# EC3mini.net
KiCad netlist of a schematic drawn in Altium Designer
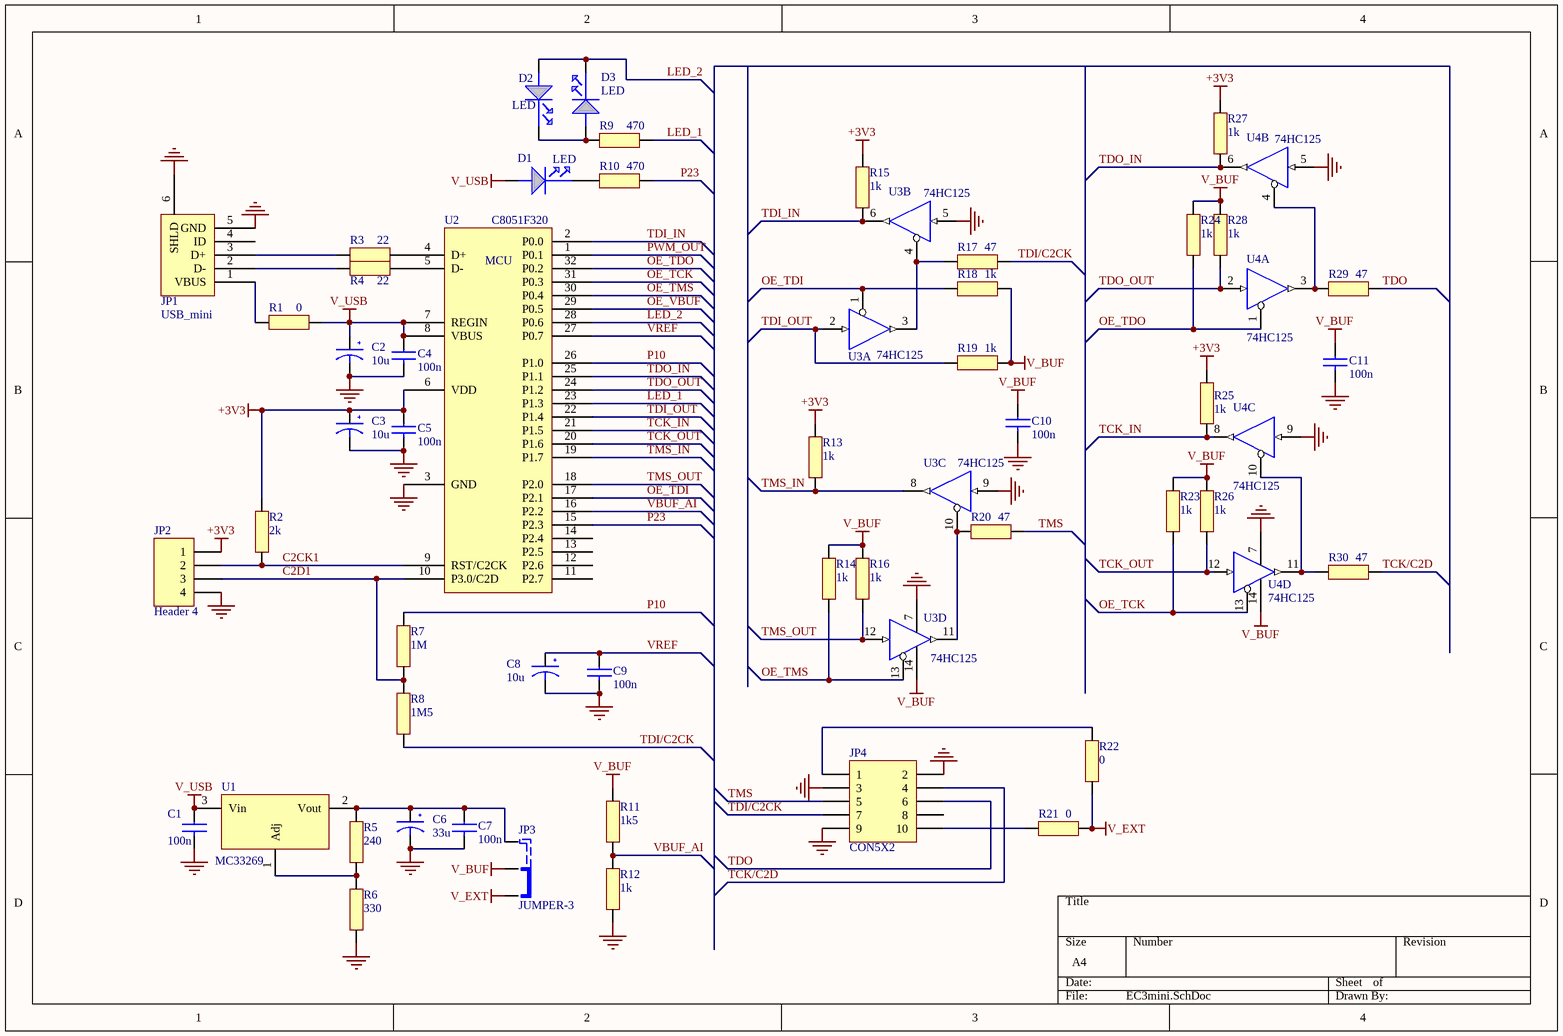
[diagram p0: EC3mini.SchDoc]

(export (version "E")
  (design (tool "Eeschema 10.0.6"))
  (components
    (comp (ref "C1") (value "100n") (footprint "C-0805") (libsource (lib "RCS-Discret") (part "C")))
    (comp (ref "C2") (value "10u") (footprint "TANTAL-A") (libsource (lib "RCS-Discret") (part "C-EL-TAN")))
    (comp (ref "C3") (value "10u") (footprint "TANTAL-A") (libsource (lib "RCS-Discret") (part "C-EL-TAN")))
    (comp (ref "C4") (value "100n") (footprint "C-0805") (libsource (lib "RCS-Discret") (part "C")))
    (comp (ref "C5") (value "100n") (footprint "C-0805") (libsource (lib "RCS-Discret") (part "C")))
    (comp (ref "C6")
      (value "33u")
      (footprint "TANTAL-B(3528)")
      (libsource (lib "RCS-Discret") (part "C-EL-TAN"))
    )
    (comp (ref "C7") (value "100n") (footprint "C-0805") (libsource (lib "RCS-Discret") (part "C")))
    (comp (ref "C8") (value "10u") (footprint "TANTAL-A") (libsource (lib "RCS-Discret") (part "C-EL-TAN")))
    (comp (ref "C9") (value "100n") (footprint "C-0805") (libsource (lib "RCS-Discret") (part "C")))
    (comp (ref "C10") (value "100n") (footprint "C-0805") (libsource (lib "RCS-Discret") (part "C")))
    (comp (ref "C11") (value "100n") (footprint "C-0805") (libsource (lib "RCS-Discret") (part "C")))
    (comp (ref "D1") (value "LED") (footprint "LED-DIP-1") (libsource (lib "RCS-Discret") (part "LED")))
    (comp (ref "D2") (value "LED") (footprint "LED-DIP-1") (libsource (lib "RCS-Discret") (part "LED")))
    (comp (ref "D3") (value "LED") (footprint "LED-DIP-1") (libsource (lib "RCS-Discret") (part "LED")))
    (comp (ref "JP1")
      (value "USB_mini")
      (footprint "miniUSBsmd")
      (libsource (lib "ISPMKII") (part "USB_mini"))
    )
    (comp (ref "JP2")
      (value "Header 4")
      (footprint "HDR1X4")
      (description "Header, 4-Pin")
      (fields (field (name "PUBLISHER") "Altium Limited"))
      (libsource (lib "Miscellaneous Connectors") (part "Header 4"))
    )
    (comp (ref "JP3")
      (value "JUMPER-3")
      (footprint "IDC1-3P")
      (description "Jumper")
      (libsource (lib "RCS-Connect&pushe") (part "JUMPER-3"))
    )
    (comp (ref "JP4")
      (value "CON5X2")
      (footprint "IDC2-5P")
      (libsource (lib "RCS-Connect&pushe") (part "CON5X2"))
    )
    (comp (ref "R1") (value "0") (footprint "R-1206") (libsource (lib "") (part "R_1")))
    (comp (ref "R2") (value "2k") (footprint "R-0805") (libsource (lib "RCS-Discret") (part "R")))
    (comp (ref "R3") (value "22") (footprint "R-0805") (libsource (lib "") (part "R_1")))
    (comp (ref "R4") (value "22") (footprint "R-0805") (libsource (lib "") (part "R_1")))
    (comp (ref "R5") (value "240") (footprint "R-0805") (libsource (lib "RCS-Discret") (part "R")))
    (comp (ref "R6") (value "330") (footprint "R-0805") (libsource (lib "RCS-Discret") (part "R")))
    (comp (ref "R7") (value "1M") (footprint "R-0805") (libsource (lib "RCS-Discret") (part "R")))
    (comp (ref "R8") (value "1M5") (footprint "R-0805") (libsource (lib "RCS-Discret") (part "R")))
    (comp (ref "R9") (value "470") (footprint "R-0805") (libsource (lib "") (part "R_1")))
    (comp (ref "R10") (value "470") (footprint "R-0805") (libsource (lib "") (part "R_1")))
    (comp (ref "R11") (value "1k5") (footprint "R-0805") (libsource (lib "RCS-Discret") (part "R")))
    (comp (ref "R12") (value "1k") (footprint "R-0805") (libsource (lib "RCS-Discret") (part "R")))
    (comp (ref "R13") (value "1k") (footprint "R-0805") (libsource (lib "RCS-Discret") (part "R")))
    (comp (ref "R14") (value "1k") (footprint "R-0805") (libsource (lib "RCS-Discret") (part "R")))
    (comp (ref "R15") (value "1k") (footprint "R-0805") (libsource (lib "RCS-Discret") (part "R")))
    (comp (ref "R16") (value "1k") (footprint "R-0805") (libsource (lib "RCS-Discret") (part "R")))
    (comp (ref "R17") (value "47") (footprint "R-0805") (libsource (lib "") (part "R_1")))
    (comp (ref "R18") (value "1k") (footprint "R-0805") (libsource (lib "") (part "R_1")))
    (comp (ref "R19") (value "1k") (footprint "R-0805") (libsource (lib "") (part "R_1")))
    (comp (ref "R20") (value "47") (footprint "R-0805") (libsource (lib "") (part "R_1")))
    (comp (ref "R21") (value "0") (footprint "R-0805") (libsource (lib "") (part "R_1")))
    (comp (ref "R22") (value "0") (footprint "R-0805") (libsource (lib "RCS-Discret") (part "R")))
    (comp (ref "R23") (value "1k") (footprint "R-0805") (libsource (lib "RCS-Discret") (part "R")))
    (comp (ref "R24") (value "1k") (footprint "R-0805") (libsource (lib "RCS-Discret") (part "R")))
    (comp (ref "R25") (value "1k") (footprint "R-0805") (libsource (lib "RCS-Discret") (part "R")))
    (comp (ref "R26") (value "1k") (footprint "R-0805") (libsource (lib "RCS-Discret") (part "R")))
    (comp (ref "R27") (value "1k") (footprint "R-0805") (libsource (lib "RCS-Discret") (part "R")))
    (comp (ref "R28") (value "1k") (footprint "R-0805") (libsource (lib "RCS-Discret") (part "R")))
    (comp (ref "R29") (value "47") (footprint "R-0805") (libsource (lib "") (part "R_1")))
    (comp (ref "R30") (value "47") (footprint "R-0805") (libsource (lib "") (part "R_1")))
    (comp (ref "U1")
      (value "MC33269")
      (footprint "SOT-428-(D-PAK)")
      (description "low dropout adjustable positive voltage regulators")
      (libsource (lib "RCS-IMS") (part "MC33269"))
    )
    (comp (ref "U2") (value "C8051F320") (footprint "QFP32") (libsource (lib "RCS-IMS") (part "C8051F320")))
    (comp (ref "U3")
      (value "74HC125")
      (footprint "SO14-(SOT-108-1)")
      (description "Four Buffers with Enable for HiZ state output")
      (libsource (lib "RCS-IMS") (part "74HC125"))
    )
    (comp (ref "U4")
      (value "74HC125")
      (footprint "SO14-(SOT-108-1)")
      (description "Four Buffers with Enable for HiZ state output")
      (libsource (lib "RCS-IMS") (part "74HC125"))
    )
  )
  (nets
    (net (code "1") (name "+3V3") (class "Default")
      (node (ref "C3") (pin "2") (pinfunction "+_2") (pintype "passive"))
      (node (ref "C5") (pin "1") (pinfunction "1_1") (pintype "passive"))
      (node (ref "JP2") (pin "1") (pinfunction "1_1") (pintype "passive"))
      (node (ref "R13") (pin "1") (pinfunction "1_1") (pintype "passive"))
      (node (ref "R15") (pin "1") (pinfunction "1_1") (pintype "passive"))
      (node (ref "R2") (pin "1") (pinfunction "1_1") (pintype "passive"))
      (node (ref "R25") (pin "1") (pinfunction "1_1") (pintype "passive"))
      (node (ref "R27") (pin "1") (pinfunction "1_1") (pintype "passive"))
      (node (ref "U2") (pin "6") (pinfunction "VDD_6") (pintype "passive"))
    )
    (net (code "2") (name "/C2CK1") (class "Default")
      (node (ref "JP2") (pin "2") (pinfunction "2_2") (pintype "passive"))
      (node (ref "R2") (pin "2") (pinfunction "2_2") (pintype "passive"))
      (node (ref "U2") (pin "9") (pinfunction "RST/C2CK_9") (pintype "passive"))
    )
    (net (code "3") (name "/C2D1") (class "Default")
      (node (ref "JP2") (pin "3") (pinfunction "3_3") (pintype "passive"))
      (node (ref "R7") (pin "2") (pinfunction "2_2") (pintype "passive"))
      (node (ref "R8") (pin "1") (pinfunction "1_1") (pintype "passive"))
      (node (ref "U2") (pin "10") (pinfunction "P3.0/C2D_10") (pintype "passive"))
    )
    (net (code "4") (name "/LED_1") (class "Default")
      (node (ref "R9") (pin "2") (pinfunction "2_2") (pintype "passive"))
      (node (ref "U2") (pin "23") (pinfunction "P1.3_23") (pintype "passive"))
    )
    (net (code "5") (name "/LED_2") (class "Default")
      (node (ref "D2") (pin "A") (pinfunction "ANODE_A") (pintype "passive"))
      (node (ref "D3") (pin "K") (pinfunction "CATHODE_K") (pintype "passive"))
      (node (ref "U2") (pin "28") (pinfunction "P0.6_28") (pintype "passive"))
    )
    (net (code "6") (name "/OE_TCK") (class "Default")
      (node (ref "R23") (pin "2") (pinfunction "2_2") (pintype "passive"))
      (node (ref "U2") (pin "31") (pinfunction "P0.3_31") (pintype "passive"))
      (node (ref "U4") (pin "13") (pinfunction "~{-Ed}_13") (pintype "passive"))
    )
    (net (code "7") (name "/OE_TDI") (class "Default")
      (node (ref "R18") (pin "1") (pinfunction "1_1") (pintype "passive"))
      (node (ref "U2") (pin "17") (pinfunction "P2.1_17") (pintype "passive"))
      (node (ref "U3") (pin "1") (pinfunction "~{-Ea}_1") (pintype "passive"))
    )
    (net (code "8") (name "/OE_TDO") (class "Default")
      (node (ref "R24") (pin "2") (pinfunction "2_2") (pintype "passive"))
      (node (ref "U2") (pin "32") (pinfunction "P0.2_32") (pintype "passive"))
      (node (ref "U4") (pin "1") (pinfunction "~{-Ea}_1") (pintype "passive"))
    )
    (net (code "9") (name "/OE_TMS") (class "Default")
      (node (ref "R14") (pin "2") (pinfunction "2_2") (pintype "passive"))
      (node (ref "U2") (pin "30") (pinfunction "P0.4_30") (pintype "passive"))
      (node (ref "U3") (pin "13") (pinfunction "~{-Ed}_13") (pintype "passive"))
    )
    (net (code "10") (name "/OE_VBUF") (class "Default")
      (node (ref "U2") (pin "29") (pinfunction "P0.5_29") (pintype "passive"))
    )
    (net (code "11") (name "/P10") (class "Default")
      (node (ref "R7") (pin "1") (pinfunction "1_1") (pintype "passive"))
      (node (ref "U2") (pin "26") (pinfunction "P1.0_26") (pintype "passive"))
    )
    (net (code "12") (name "/P23") (class "Default")
      (node (ref "R10") (pin "2") (pinfunction "2_2") (pintype "passive"))
      (node (ref "U2") (pin "15") (pinfunction "P2.3_15") (pintype "passive"))
    )
    (net (code "13") (name "/PWM_OUT") (class "Default")
      (node (ref "U2") (pin "1") (pinfunction "P0.1_1") (pintype "passive"))
    )
    (net (code "14") (name "/TCK_IN") (class "Default")
      (node (ref "R25") (pin "2") (pinfunction "2_2") (pintype "passive"))
      (node (ref "U2") (pin "21") (pinfunction "P1.5_21") (pintype "passive"))
      (node (ref "U4") (pin "8") (pinfunction "Yc_8") (pintype "output"))
    )
    (net (code "15") (name "/TCK_OUT") (class "Default")
      (node (ref "R26") (pin "2") (pinfunction "2_2") (pintype "passive"))
      (node (ref "U2") (pin "20") (pinfunction "P1.6_20") (pintype "passive"))
      (node (ref "U4") (pin "12") (pinfunction "D_12") (pintype "input"))
    )
    (net (code "16") (name "/TCK{slash}C2D") (class "Default")
      (node (ref "JP4") (pin "4") (pinfunction "4_4") (pintype "passive"))
      (node (ref "R30") (pin "2") (pinfunction "2_2") (pintype "passive"))
    )
    (net (code "17") (name "/TDI_IN") (class "Default")
      (node (ref "R15") (pin "2") (pinfunction "2_2") (pintype "passive"))
      (node (ref "U2") (pin "2") (pinfunction "P0.0_2") (pintype "passive"))
      (node (ref "U3") (pin "6") (pinfunction "Yb_6") (pintype "output"))
    )
    (net (code "18") (name "/TDI_OUT") (class "Default")
      (node (ref "R19") (pin "1") (pinfunction "1_1") (pintype "passive"))
      (node (ref "U2") (pin "22") (pinfunction "P1.4_22") (pintype "passive"))
      (node (ref "U3") (pin "2") (pinfunction "A_2") (pintype "input"))
    )
    (net (code "19") (name "/TDI{slash}C2CK") (class "Default")
      (node (ref "JP4") (pin "7") (pinfunction "7_7") (pintype "passive"))
      (node (ref "R17") (pin "2") (pinfunction "2_2") (pintype "passive"))
      (node (ref "R8") (pin "2") (pinfunction "2_2") (pintype "passive"))
    )
    (net (code "20") (name "/TDO") (class "Default")
      (node (ref "JP4") (pin "6") (pinfunction "6_6") (pintype "passive"))
      (node (ref "R29") (pin "2") (pinfunction "2_2") (pintype "passive"))
    )
    (net (code "21") (name "/TDO_IN") (class "Default")
      (node (ref "R27") (pin "2") (pinfunction "2_2") (pintype "passive"))
      (node (ref "U2") (pin "25") (pinfunction "P1.1_25") (pintype "passive"))
      (node (ref "U4") (pin "6") (pinfunction "Yb_6") (pintype "output"))
    )
    (net (code "22") (name "/TDO_OUT") (class "Default")
      (node (ref "R28") (pin "2") (pinfunction "2_2") (pintype "passive"))
      (node (ref "U2") (pin "24") (pinfunction "P1.2_24") (pintype "passive"))
      (node (ref "U4") (pin "2") (pinfunction "A_2") (pintype "input"))
    )
    (net (code "23") (name "/TMS") (class "Default")
      (node (ref "JP4") (pin "5") (pinfunction "5_5") (pintype "passive"))
      (node (ref "R20") (pin "2") (pinfunction "2_2") (pintype "passive"))
    )
    (net (code "24") (name "/TMS_IN") (class "Default")
      (node (ref "R13") (pin "2") (pinfunction "2_2") (pintype "passive"))
      (node (ref "U2") (pin "19") (pinfunction "P1.7_19") (pintype "passive"))
      (node (ref "U3") (pin "8") (pinfunction "Yc_8") (pintype "output"))
    )
    (net (code "25") (name "/TMS_OUT") (class "Default")
      (node (ref "R16") (pin "2") (pinfunction "2_2") (pintype "passive"))
      (node (ref "U2") (pin "18") (pinfunction "P2.0_18") (pintype "passive"))
      (node (ref "U3") (pin "12") (pinfunction "D_12") (pintype "input"))
    )
    (net (code "26") (name "/VBUF_AI") (class "Default")
      (node (ref "R11") (pin "2") (pinfunction "2_2") (pintype "passive"))
      (node (ref "R12") (pin "1") (pinfunction "1_1") (pintype "passive"))
      (node (ref "U2") (pin "16") (pinfunction "P2.2_16") (pintype "passive"))
    )
    (net (code "27") (name "/VREF") (class "Default")
      (node (ref "C8") (pin "2") (pinfunction "+_2") (pintype "passive"))
      (node (ref "C9") (pin "1") (pinfunction "1_1") (pintype "passive"))
      (node (ref "U2") (pin "27") (pinfunction "P0.7_27") (pintype "passive"))
    )
    (net (code "28") (name "GND") (class "Default")
      (node (ref "C1") (pin "2") (pinfunction "2_2") (pintype "passive"))
      (node (ref "C10") (pin "2") (pinfunction "2_2") (pintype "passive"))
      (node (ref "C11") (pin "2") (pinfunction "2_2") (pintype "passive"))
      (node (ref "C2") (pin "1") (pinfunction "-_1") (pintype "passive"))
      (node (ref "C3") (pin "1") (pinfunction "-_1") (pintype "passive"))
      (node (ref "C4") (pin "2") (pinfunction "2_2") (pintype "passive"))
      (node (ref "C5") (pin "2") (pinfunction "2_2") (pintype "passive"))
      (node (ref "C6") (pin "1") (pinfunction "-_1") (pintype "passive"))
      (node (ref "C7") (pin "2") (pinfunction "2_2") (pintype "passive"))
      (node (ref "C8") (pin "1") (pinfunction "-_1") (pintype "passive"))
      (node (ref "C9") (pin "2") (pinfunction "2_2") (pintype "passive"))
      (node (ref "JP1") (pin "5") (pinfunction "GND_5") (pintype "passive"))
      (node (ref "JP1") (pin "6") (pinfunction "SHLD_6") (pintype "passive"))
      (node (ref "JP2") (pin "4") (pinfunction "4_4") (pintype "passive"))
      (node (ref "JP4") (pin "2") (pinfunction "2_2") (pintype "passive"))
      (node (ref "JP4") (pin "3") (pinfunction "3_3") (pintype "passive"))
      (node (ref "JP4") (pin "9") (pinfunction "9_9") (pintype "passive"))
      (node (ref "R12") (pin "2") (pinfunction "2_2") (pintype "passive"))
      (node (ref "R6") (pin "2") (pinfunction "2_2") (pintype "passive"))
      (node (ref "U2") (pin "3") (pinfunction "GND_3") (pintype "passive"))
      (node (ref "U3") (pin "5") (pinfunction "B_5") (pintype "input"))
      (node (ref "U3") (pin "7") (pinfunction "GND-D_7") (pintype "power_in"))
      (node (ref "U3") (pin "9") (pinfunction "C_9") (pintype "input"))
      (node (ref "U4") (pin "5") (pinfunction "B_5") (pintype "input"))
      (node (ref "U4") (pin "7") (pinfunction "GND-D_7") (pintype "power_in"))
      (node (ref "U4") (pin "9") (pinfunction "C_9") (pintype "input"))
    )
    (net (code "29") (name "Net-(C6-+)") (class "Default")
      (node (ref "C6") (pin "2") (pinfunction "+_2") (pintype "passive"))
      (node (ref "C7") (pin "1") (pinfunction "1_1") (pintype "passive"))
      (node (ref "JP3") (pin "3") (pinfunction "3_3") (pintype "passive"))
      (node (ref "R5") (pin "1") (pinfunction "1_1") (pintype "passive"))
      (node (ref "U1") (pin "2") (pinfunction "Vout_2") (pintype "passive"))
    )
    (net (code "30") (name "Net-(D1-CATHODE)") (class "Default")
      (node (ref "D1") (pin "K") (pinfunction "CATHODE_K") (pintype "passive"))
      (node (ref "R10") (pin "1") (pinfunction "1_1") (pintype "passive"))
    )
    (net (code "31") (name "Net-(D2-CATHODE)") (class "Default")
      (node (ref "D2") (pin "K") (pinfunction "CATHODE_K") (pintype "passive"))
      (node (ref "D3") (pin "A") (pinfunction "ANODE_A") (pintype "passive"))
      (node (ref "R9") (pin "1") (pinfunction "1_1") (pintype "passive"))
    )
    (net (code "32") (name "Net-(JP1-D+)") (class "Default")
      (node (ref "JP1") (pin "3") (pinfunction "D+_3") (pintype "passive"))
      (node (ref "R3") (pin "1") (pinfunction "1_1") (pintype "passive"))
    )
    (net (code "33") (name "Net-(JP1-D-)") (class "Default")
      (node (ref "JP1") (pin "2") (pinfunction "D-_2") (pintype "passive"))
      (node (ref "R4") (pin "1") (pinfunction "1_1") (pintype "passive"))
    )
    (net (code "34") (name "Net-(JP1-VBUS)") (class "Default")
      (node (ref "JP1") (pin "1") (pinfunction "VBUS_1") (pintype "passive"))
      (node (ref "R1") (pin "1") (pinfunction "1_1") (pintype "passive"))
    )
    (net (code "35") (name "Net-(JP4-Pad1)") (class "Default")
      (node (ref "JP4") (pin "1") (pinfunction "1_1") (pintype "passive"))
      (node (ref "R22") (pin "1") (pinfunction "1_1") (pintype "passive"))
    )
    (net (code "36") (name "Net-(JP4-Pad10)") (class "Default")
      (node (ref "JP4") (pin "10") (pinfunction "10_10") (pintype "passive"))
      (node (ref "R21") (pin "1") (pinfunction "1_1") (pintype "passive"))
    )
    (net (code "37") (name "Net-(U1-Adj)") (class "Default")
      (node (ref "R5") (pin "2") (pinfunction "2_2") (pintype "passive"))
      (node (ref "R6") (pin "1") (pinfunction "1_1") (pintype "passive"))
      (node (ref "U1") (pin "1") (pinfunction "Adj_1") (pintype "passive"))
    )
    (net (code "38") (name "Net-(U2-D+)") (class "Default")
      (node (ref "R3") (pin "2") (pinfunction "2_2") (pintype "passive"))
      (node (ref "U2") (pin "4") (pinfunction "D+_4") (pintype "passive"))
    )
    (net (code "39") (name "Net-(U2-D-)") (class "Default")
      (node (ref "R4") (pin "2") (pinfunction "2_2") (pintype "passive"))
      (node (ref "U2") (pin "5") (pinfunction "D-_5") (pintype "passive"))
    )
    (net (code "40") (name "Net-(U3A-Ya)") (class "Default")
      (node (ref "R17") (pin "1") (pinfunction "1_1") (pintype "passive"))
      (node (ref "U3") (pin "3") (pinfunction "Ya_3") (pintype "output"))
      (node (ref "U3") (pin "4") (pinfunction "~{-Eb}_4") (pintype "passive"))
    )
    (net (code "41") (name "Net-(U3C-~{-Ec})") (class "Default")
      (node (ref "R20") (pin "1") (pinfunction "1_1") (pintype "passive"))
      (node (ref "U3") (pin "10") (pinfunction "~{-Ec}_10") (pintype "passive"))
      (node (ref "U3") (pin "11") (pinfunction "Yd_11") (pintype "output"))
    )
    (net (code "42") (name "Net-(U4A-Ya)") (class "Default")
      (node (ref "R29") (pin "1") (pinfunction "1_1") (pintype "passive"))
      (node (ref "U4") (pin "3") (pinfunction "Ya_3") (pintype "output"))
      (node (ref "U4") (pin "4") (pinfunction "~{-Eb}_4") (pintype "passive"))
    )
    (net (code "43") (name "Net-(U4C-~{-Ec})") (class "Default")
      (node (ref "R30") (pin "1") (pinfunction "1_1") (pintype "passive"))
      (node (ref "U4") (pin "10") (pinfunction "~{-Ec}_10") (pintype "passive"))
      (node (ref "U4") (pin "11") (pinfunction "Yd_11") (pintype "output"))
    )
    (net (code "44") (name "V_BUF") (class "Default")
      (node (ref "C10") (pin "1") (pinfunction "1_1") (pintype "passive"))
      (node (ref "C11") (pin "1") (pinfunction "1_1") (pintype "passive"))
      (node (ref "JP3") (pin "2") (pinfunction "2_2") (pintype "passive"))
      (node (ref "R11") (pin "1") (pinfunction "1_1") (pintype "passive"))
      (node (ref "R14") (pin "1") (pinfunction "1_1") (pintype "passive"))
      (node (ref "R16") (pin "1") (pinfunction "1_1") (pintype "passive"))
      (node (ref "R18") (pin "2") (pinfunction "2_2") (pintype "passive"))
      (node (ref "R19") (pin "2") (pinfunction "2_2") (pintype "passive"))
      (node (ref "R23") (pin "1") (pinfunction "1_1") (pintype "passive"))
      (node (ref "R24") (pin "1") (pinfunction "1_1") (pintype "passive"))
      (node (ref "R26") (pin "1") (pinfunction "1_1") (pintype "passive"))
      (node (ref "R28") (pin "1") (pinfunction "1_1") (pintype "passive"))
      (node (ref "U3") (pin "14") (pinfunction "VCC_14") (pintype "power_in"))
      (node (ref "U4") (pin "14") (pinfunction "VCC_14") (pintype "power_in"))
    )
    (net (code "45") (name "V_EXT") (class "Default")
      (node (ref "JP3") (pin "1") (pinfunction "1_1") (pintype "passive"))
      (node (ref "R21") (pin "2") (pinfunction "2_2") (pintype "passive"))
      (node (ref "R22") (pin "2") (pinfunction "2_2") (pintype "passive"))
    )
    (net (code "46") (name "V_USB") (class "Default")
      (node (ref "C1") (pin "1") (pinfunction "1_1") (pintype "passive"))
      (node (ref "C2") (pin "2") (pinfunction "+_2") (pintype "passive"))
      (node (ref "C4") (pin "1") (pinfunction "1_1") (pintype "passive"))
      (node (ref "D1") (pin "A") (pinfunction "ANODE_A") (pintype "passive"))
      (node (ref "R1") (pin "2") (pinfunction "2_2") (pintype "passive"))
      (node (ref "U1") (pin "3") (pinfunction "Vin_3") (pintype "passive"))
      (node (ref "U2") (pin "7") (pinfunction "REGIN_7") (pintype "passive"))
      (node (ref "U2") (pin "8") (pinfunction "VBUS_8") (pintype "passive"))
    )
    (net (code "47") (name "unconnected-(JP1-ID-Pad4)") (class "Default")
      (node (ref "JP1") (pin "4") (pinfunction "ID_4") (pintype "passive"))
    )
    (net (code "48") (name "unconnected-(JP4-Pad8)") (class "Default")
      (node (ref "JP4") (pin "8") (pinfunction "8_8") (pintype "passive"))
    )
    (net (code "49") (name "unconnected-(U2-P2.4-Pad14)") (class "Default")
      (node (ref "U2") (pin "14") (pinfunction "P2.4_14") (pintype "passive"))
    )
    (net (code "50") (name "unconnected-(U2-P2.5-Pad13)") (class "Default")
      (node (ref "U2") (pin "13") (pinfunction "P2.5_13") (pintype "passive"))
    )
    (net (code "51") (name "unconnected-(U2-P2.6-Pad12)") (class "Default")
      (node (ref "U2") (pin "12") (pinfunction "P2.6_12") (pintype "passive"))
    )
    (net (code "52") (name "unconnected-(U2-P2.7-Pad11)") (class "Default")
      (node (ref "U2") (pin "11") (pinfunction "P2.7_11") (pintype "passive"))
    )
  )
)
